# ETH_PHY_RGMII.net
KiCad netlist of a schematic drawn in Altium Designer
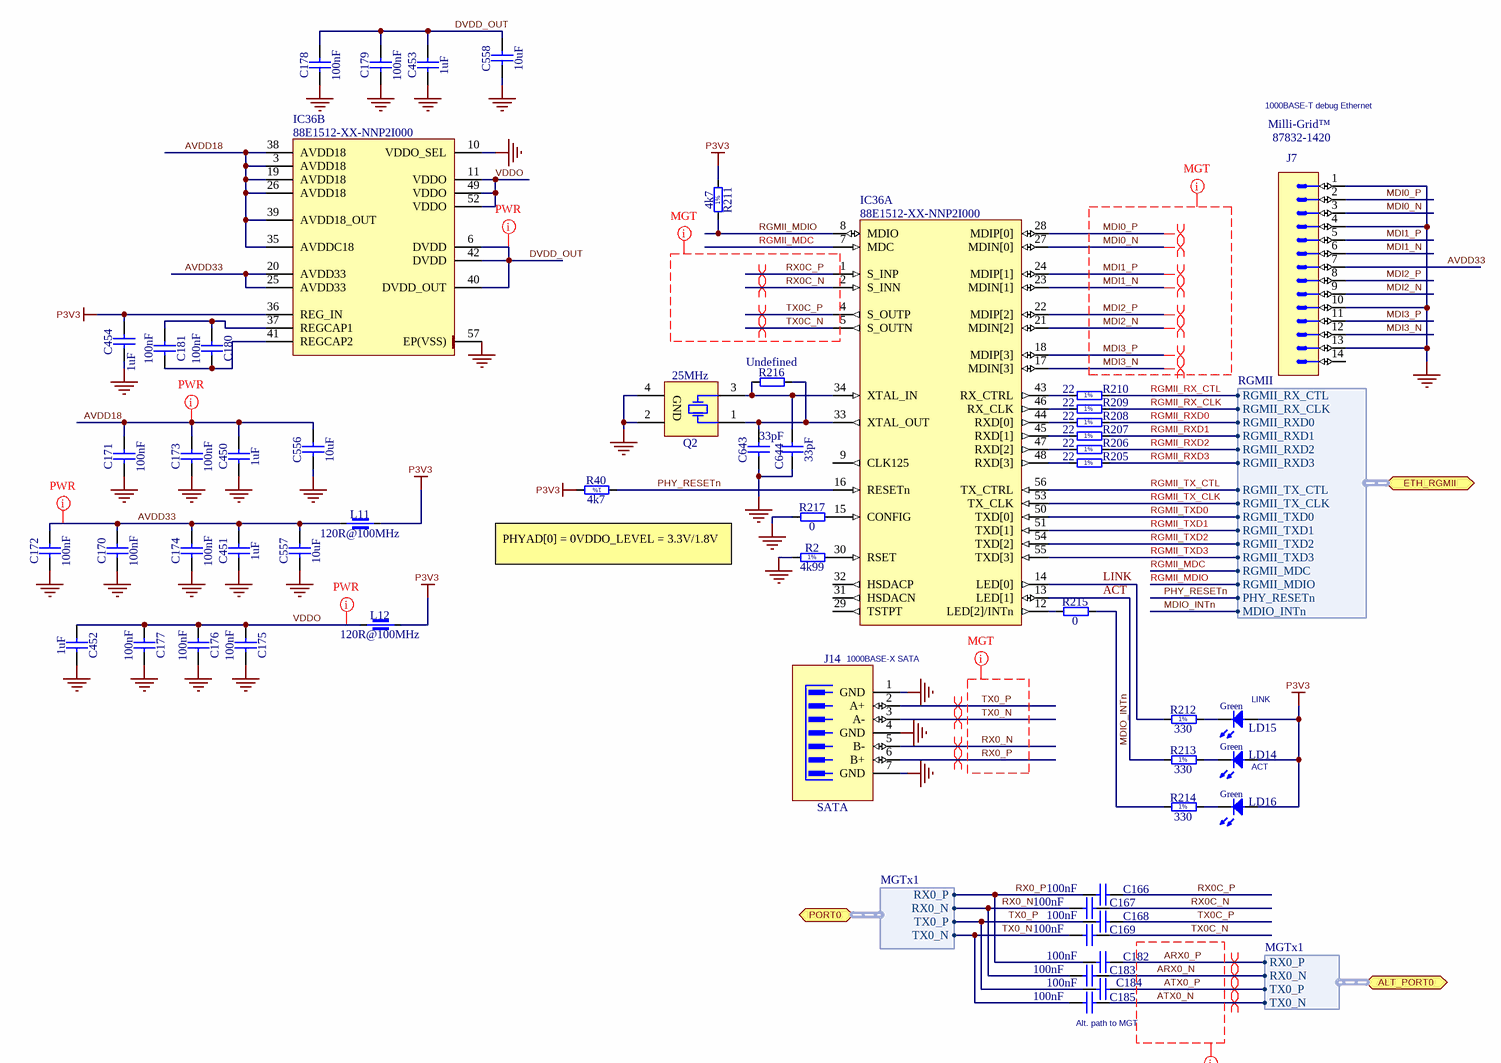
[diagram p0: ETH_PHY_RGMII.SchDoc]

(export (version "E")
  (design (tool "Eeschema 10.0.6"))
  (components
    (comp (ref "C166")
      (value "100nF")
      (footprint "CAPC0603X33N")
      (description "Non-polarised capacitor")
      (fields
        (field (name "MANUFACTURER PART NUMBER") "CC0201_100NF_6.3V_10%_X5R")
        (field (name "MANUFACTURER") "GENERIC")
        (field (name "AUTHOR") "CERN DEM JLC")
      )
      (libsource (lib "Capacitors") (part "Capacitor - non polarized"))
    )
    (comp (ref "C167")
      (value "100nF")
      (footprint "CAPC0603X33N")
      (description "Non-polarised capacitor")
      (fields
        (field (name "MANUFACTURER PART NUMBER") "CC0201_100NF_6.3V_10%_X5R")
        (field (name "MANUFACTURER") "GENERIC")
        (field (name "AUTHOR") "CERN DEM JLC")
      )
      (libsource (lib "Capacitors") (part "Capacitor - non polarized"))
    )
    (comp (ref "C168")
      (value "100nF")
      (footprint "CAPC0603X33N")
      (description "Non-polarised capacitor")
      (fields
        (field (name "MANUFACTURER PART NUMBER") "CC0201_100NF_6.3V_10%_X5R")
        (field (name "MANUFACTURER") "GENERIC")
        (field (name "AUTHOR") "CERN DEM JLC")
      )
      (libsource (lib "Capacitors") (part "Capacitor - non polarized"))
    )
    (comp (ref "C169")
      (value "100nF")
      (footprint "CAPC0603X33N")
      (description "Non-polarised capacitor")
      (fields
        (field (name "MANUFACTURER PART NUMBER") "CC0201_100NF_6.3V_10%_X5R")
        (field (name "MANUFACTURER") "GENERIC")
        (field (name "AUTHOR") "CERN DEM JLC")
      )
      (libsource (lib "Capacitors") (part "Capacitor - non polarized"))
    )
    (comp (ref "C170")
      (value "100nF")
      (footprint "CAPC0603X33N")
      (description "Non-polarised capacitor")
      (fields
        (field (name "MANUFACTURER PART NUMBER") "CC0201_100NF_6.3V_10%_X5R")
        (field (name "MANUFACTURER") "GENERIC")
        (field (name "AUTHOR") "CERN DEM JLC")
      )
      (libsource (lib "Capacitors") (part "Capacitor - non polarized"))
    )
    (comp (ref "C171")
      (value "100nF")
      (footprint "CAPC0603X33N")
      (description "Non-polarised capacitor")
      (fields
        (field (name "MANUFACTURER PART NUMBER") "CC0201_100NF_6.3V_10%_X5R")
        (field (name "MANUFACTURER") "GENERIC")
        (field (name "AUTHOR") "CERN DEM JLC")
      )
      (libsource (lib "Capacitors") (part "Capacitor - non polarized"))
    )
    (comp (ref "C172")
      (value "100nF")
      (footprint "CAPC0603X33N")
      (description "Non-polarised capacitor")
      (fields
        (field (name "MANUFACTURER PART NUMBER") "CC0201_100NF_6.3V_10%_X5R")
        (field (name "MANUFACTURER") "GENERIC")
        (field (name "AUTHOR") "CERN DEM JLC")
      )
      (libsource (lib "Capacitors") (part "Capacitor - non polarized"))
    )
    (comp (ref "C173")
      (value "100nF")
      (footprint "CAPC0603X33N")
      (description "Non-polarised capacitor")
      (fields
        (field (name "MANUFACTURER PART NUMBER") "CC0201_100NF_6.3V_10%_X5R")
        (field (name "MANUFACTURER") "GENERIC")
        (field (name "AUTHOR") "CERN DEM JLC")
      )
      (libsource (lib "Capacitors") (part "Capacitor - non polarized"))
    )
    (comp (ref "C174")
      (value "100nF")
      (footprint "CAPC0603X33N")
      (description "Non-polarised capacitor")
      (fields
        (field (name "MANUFACTURER PART NUMBER") "CC0201_100NF_6.3V_10%_X5R")
        (field (name "MANUFACTURER") "GENERIC")
        (field (name "AUTHOR") "CERN DEM JLC")
      )
      (libsource (lib "Capacitors") (part "Capacitor - non polarized"))
    )
    (comp (ref "C175")
      (value "100nF")
      (footprint "CAPC0603X33N")
      (description "Non-polarised capacitor")
      (fields
        (field (name "MANUFACTURER PART NUMBER") "CC0201_100NF_6.3V_10%_X5R")
        (field (name "MANUFACTURER") "GENERIC")
        (field (name "AUTHOR") "CERN DEM JLC")
      )
      (libsource (lib "Capacitors") (part "Capacitor - non polarized"))
    )
    (comp (ref "C176")
      (value "100nF")
      (footprint "CAPC0603X33N")
      (description "Non-polarised capacitor")
      (fields
        (field (name "MANUFACTURER PART NUMBER") "CC0201_100NF_6.3V_10%_X5R")
        (field (name "MANUFACTURER") "GENERIC")
        (field (name "AUTHOR") "CERN DEM JLC")
      )
      (libsource (lib "Capacitors") (part "Capacitor - non polarized"))
    )
    (comp (ref "C177")
      (value "100nF")
      (footprint "CAPC0603X33N")
      (description "Non-polarised capacitor")
      (fields
        (field (name "MANUFACTURER PART NUMBER") "CC0201_100NF_6.3V_10%_X5R")
        (field (name "MANUFACTURER") "GENERIC")
        (field (name "AUTHOR") "CERN DEM JLC")
      )
      (libsource (lib "Capacitors") (part "Capacitor - non polarized"))
    )
    (comp (ref "C178")
      (value "100nF")
      (footprint "CAPC0603X33N")
      (description "Non-polarised capacitor")
      (fields
        (field (name "MANUFACTURER PART NUMBER") "CC0201_100NF_6.3V_10%_X5R")
        (field (name "MANUFACTURER") "GENERIC")
        (field (name "AUTHOR") "CERN DEM JLC")
      )
      (libsource (lib "Capacitors") (part "Capacitor - non polarized"))
    )
    (comp (ref "C179")
      (value "100nF")
      (footprint "CAPC0603X33N")
      (description "Non-polarised capacitor")
      (fields
        (field (name "MANUFACTURER PART NUMBER") "CC0201_100NF_6.3V_10%_X5R")
        (field (name "MANUFACTURER") "GENERIC")
        (field (name "AUTHOR") "CERN DEM JLC")
      )
      (libsource (lib "Capacitors") (part "Capacitor - non polarized"))
    )
    (comp (ref "C180")
      (value "100nF")
      (footprint "CAPC0603X33N")
      (description "Non-polarised capacitor")
      (fields
        (field (name "MANUFACTURER PART NUMBER") "CC0201_100NF_6.3V_10%_X5R")
        (field (name "MANUFACTURER") "GENERIC")
        (field (name "AUTHOR") "CERN DEM JLC")
      )
      (libsource (lib "Capacitors") (part "Capacitor - non polarized"))
    )
    (comp (ref "C181")
      (value "100nF")
      (footprint "CAPC0603X33N")
      (description "Non-polarised capacitor")
      (fields
        (field (name "MANUFACTURER PART NUMBER") "CC0201_100NF_6.3V_10%_X5R")
        (field (name "MANUFACTURER") "GENERIC")
        (field (name "AUTHOR") "CERN DEM JLC")
      )
      (libsource (lib "Capacitors") (part "Capacitor - non polarized"))
    )
    (comp (ref "C182")
      (value "100nF")
      (footprint "CAPC0603X33N")
      (description "Non-polarised capacitor")
      (fields
        (field (name "MANUFACTURER PART NUMBER") "CC0201_100NF_6.3V_10%_X5R")
        (field (name "MANUFACTURER") "GENERIC")
        (field (name "AUTHOR") "CERN DEM JLC")
      )
      (libsource (lib "Capacitors") (part "Capacitor - non polarized"))
    )
    (comp (ref "C183")
      (value "100nF")
      (footprint "CAPC0603X33N")
      (description "Non-polarised capacitor")
      (fields
        (field (name "MANUFACTURER PART NUMBER") "CC0201_100NF_6.3V_10%_X5R")
        (field (name "MANUFACTURER") "GENERIC")
        (field (name "AUTHOR") "CERN DEM JLC")
      )
      (libsource (lib "Capacitors") (part "Capacitor - non polarized"))
    )
    (comp (ref "C184")
      (value "100nF")
      (footprint "CAPC0603X33N")
      (description "Non-polarised capacitor")
      (fields
        (field (name "MANUFACTURER PART NUMBER") "CC0201_100NF_6.3V_10%_X5R")
        (field (name "MANUFACTURER") "GENERIC")
        (field (name "AUTHOR") "CERN DEM JLC")
      )
      (libsource (lib "Capacitors") (part "Capacitor - non polarized"))
    )
    (comp (ref "C185")
      (value "100nF")
      (footprint "CAPC0603X33N")
      (description "Non-polarised capacitor")
      (fields
        (field (name "MANUFACTURER PART NUMBER") "CC0201_100NF_6.3V_10%_X5R")
        (field (name "MANUFACTURER") "GENERIC")
        (field (name "AUTHOR") "CERN DEM JLC")
      )
      (libsource (lib "Capacitors") (part "Capacitor - non polarized"))
    )
    (comp (ref "C450")
      (value "1uF")
      (footprint "CAPC1005X55N")
      (description "Non-polarised capacitor")
      (fields
        (field (name "MANUFACTURER PART NUMBER") "CC0402_1UF_16V_10%_X5R")
        (field (name "MANUFACTURER") "GENERIC")
        (field (name "AUTHOR") "CERN DEM JLC")
      )
      (libsource (lib "Capacitors") (part "Capacitor - non polarized"))
    )
    (comp (ref "C451")
      (value "1uF")
      (footprint "CAPC1005X55N")
      (description "Non-polarised capacitor")
      (fields
        (field (name "MANUFACTURER PART NUMBER") "CC0402_1UF_16V_10%_X5R")
        (field (name "MANUFACTURER") "GENERIC")
        (field (name "AUTHOR") "CERN DEM JLC")
      )
      (libsource (lib "Capacitors") (part "Capacitor - non polarized"))
    )
    (comp (ref "C452")
      (value "1uF")
      (footprint "CAPC1005X55N")
      (description "Non-polarised capacitor")
      (fields
        (field (name "MANUFACTURER PART NUMBER") "CC0402_1UF_16V_10%_X5R")
        (field (name "MANUFACTURER") "GENERIC")
        (field (name "AUTHOR") "CERN DEM JLC")
      )
      (libsource (lib "Capacitors") (part "Capacitor - non polarized"))
    )
    (comp (ref "C453")
      (value "1uF")
      (footprint "CAPC1005X55N")
      (description "Non-polarised capacitor")
      (fields
        (field (name "MANUFACTURER PART NUMBER") "CC0402_1UF_16V_10%_X5R")
        (field (name "MANUFACTURER") "GENERIC")
        (field (name "AUTHOR") "CERN DEM JLC")
      )
      (libsource (lib "Capacitors") (part "Capacitor - non polarized"))
    )
    (comp (ref "C454")
      (value "1uF")
      (footprint "CAPC1005X55N")
      (description "Non-polarised capacitor")
      (fields
        (field (name "MANUFACTURER PART NUMBER") "CC0402_1UF_16V_10%_X5R")
        (field (name "MANUFACTURER") "GENERIC")
        (field (name "AUTHOR") "CERN DEM JLC")
      )
      (libsource (lib "Capacitors") (part "Capacitor - non polarized"))
    )
    (comp (ref "C556")
      (value "10uF")
      (footprint "CAPC1608X87N")
      (description "Non-polarised capacitor")
      (fields
        (field (name "MANUFACTURER PART NUMBER") "CC0603_10uF_6.3V_20%_X5R")
        (field (name "MANUFACTURER") "GENERIC")
        (field (name "AUTHOR") "CERN DEM JLC")
      )
      (libsource (lib "Capacitors") (part "Capacitor - non polarized"))
    )
    (comp (ref "C557")
      (value "10uF")
      (footprint "CAPC1608X87N")
      (description "Non-polarised capacitor")
      (fields
        (field (name "MANUFACTURER PART NUMBER") "CC0603_10uF_6.3V_20%_X5R")
        (field (name "MANUFACTURER") "GENERIC")
        (field (name "AUTHOR") "CERN DEM JLC")
      )
      (libsource (lib "Capacitors") (part "Capacitor - non polarized"))
    )
    (comp (ref "C558")
      (value "10uF")
      (footprint "CAPC1608X87N")
      (description "Non-polarised capacitor")
      (fields
        (field (name "MANUFACTURER PART NUMBER") "CC0603_10uF_6.3V_20%_X5R")
        (field (name "MANUFACTURER") "GENERIC")
        (field (name "AUTHOR") "CERN DEM JLC")
      )
      (libsource (lib "Capacitors") (part "Capacitor - non polarized"))
    )
    (comp (ref "C643")
      (value "33pF")
      (footprint "CAPC1005X55N")
      (description "Non-polarised capacitor")
      (fields
        (field (name "MANUFACTURER PART NUMBER") "CC0402_33PF_50V_5%_C0G")
        (field (name "MANUFACTURER") "GENERIC")
        (field (name "AUTHOR") "CERN DEM JLC")
      )
      (libsource (lib "Capacitors") (part "Capacitor - non polarized"))
    )
    (comp (ref "C644")
      (value "33pF")
      (footprint "CAPC1005X55N")
      (description "Non-polarised capacitor")
      (fields
        (field (name "MANUFACTURER PART NUMBER") "CC0402_33PF_50V_5%_C0G")
        (field (name "MANUFACTURER") "GENERIC")
        (field (name "AUTHOR") "CERN DEM JLC")
      )
      (libsource (lib "Capacitors") (part "Capacitor - non polarized"))
    )
    (comp (ref "IC36")
      (value "88E1512-XX-NNP2I000")
      (footprint "QFN50P800X800X100-57N-S437")
      (description "Alaska Integrated 10/100/1000 Mbps Energy Efficient Ethernet Transceiver")
      (fields (field (name "MANUFACTURER") "MARVELL  TECHNOLOGY") (field (name "AUTHOR") "CERN DEM JLC"))
      (libsource (lib "ICs And Semiconductors") (part "88E1512-XX-NNP2I000"))
    )
    (comp (ref "J7")
      (value "Milli-Grid™")
      (footprint "MOLEX_87832-1420")
      (description "Connector 14 Male")
      (fields
        (field (name "MANUFACTURER PART NUMBER") "87832-1420")
        (field (name "MANUFACTURER") "MOLEX")
        (field (name "PART NUMBER") "MOLEX_87832-1420")
        (field (name "AUTHOR") "CERN DEM JLC")
      )
      (libsource (lib "Connectors") (part "Connector 14 Male"))
    )
    (comp (ref "J14")
      (value "SATA")
      (footprint "MOLEX_67800-5005")
      (description "7 Pin SATA Receptacle")
      (fields
        (field (name "PART NUMBER") "MOLEX_67800-5005")
        (field (name "MANUFACTURER") "MOLEX")
        (field (name "AUTHOR") "CERN DEM MR")
      )
      (libsource (lib "Connectors") (part "Connector SATA 7 Male"))
    )
    (comp (ref "L11")
      (value "120R@100MHz")
      (footprint "INDC1005X55N")
      (fields
        (field (name "MANUFACTURER PART NUMBER") "BLM15PX121SN1D")
        (field (name "MANUFACTURER") "MURATA")
        (field (name "PART NUMBER") "IND0402_MURATA_BLM15PX121SN1D")
        (field (name "AUTHOR") "CERN DEM JMW")
      )
      (libsource (lib "Inductors & Transformers") (part "Ferrite Bead"))
    )
    (comp (ref "L12")
      (value "120R@100MHz")
      (footprint "INDC1005X55N")
      (fields
        (field (name "MANUFACTURER PART NUMBER") "BLM15PX121SN1D")
        (field (name "MANUFACTURER") "MURATA")
        (field (name "PART NUMBER") "IND0402_MURATA_BLM15PX121SN1D")
        (field (name "AUTHOR") "CERN DEM JMW")
      )
      (libsource (lib "") (part "Ferrite Bead_1"))
    )
    (comp (ref "LD14")
      (value "Green")
      (footprint "LED_AVAGO_HSME-C120")
      (description "LED Green 1C 2A")
      (fields
        (field (name "MANUFACTURER PART NUMBER") "HSME-C120")
        (field (name "MANUFACTURER") "AVAGO TECHNOLOGIES")
        (field (name "AUTHOR") "CERN DEM JMW")
      )
      (libsource (lib "ICs And Semiconductors") (part "LED Green 1C 2A"))
    )
    (comp (ref "LD15")
      (value "Green")
      (footprint "LED_AVAGO_HSME-C120")
      (description "LED Green 1C 2A")
      (fields
        (field (name "MANUFACTURER PART NUMBER") "HSME-C120")
        (field (name "MANUFACTURER") "AVAGO TECHNOLOGIES")
        (field (name "AUTHOR") "CERN DEM JMW")
      )
      (libsource (lib "ICs And Semiconductors") (part "LED Green 1C 2A"))
    )
    (comp (ref "LD16")
      (value "Green")
      (footprint "LED_AVAGO_HSME-C120")
      (description "LED Green 1C 2A")
      (fields
        (field (name "MANUFACTURER PART NUMBER") "HSME-C120")
        (field (name "MANUFACTURER") "AVAGO TECHNOLOGIES")
        (field (name "AUTHOR") "CERN DEM JMW")
      )
      (libsource (lib "ICs And Semiconductors") (part "LED Green 1C 2A"))
    )
    (comp (ref "Q2")
      (value "25MHz")
      (footprint "XTAL_TXC_8Y")
      (description "Crystal 4 pins 1=XTAL Control 2=GND3=XTAL 4=GND")
      (fields
        (field (name "MANUFACTURER PART NUMBER") "8Y-25.000MAAJ-T")
        (field (name "MANUFACTURER") "TXC CORPORATION")
        (field (name "AUTHOR") "CERN DEM JLC")
      )
      (libsource (lib "ICs And Semiconductors") (part "Quartz Crystal 1X 2GND 3X 4GND"))
    )
    (comp (ref "R2")
      (value "4k99")
      (footprint "RESC1608X55N")
      (description "Resistor - 1%")
      (fields
        (field (name "MANUFACTURER PART NUMBER") "R0603_4K99_1%_0.063W_50PPM")
        (field (name "MANUFACTURER") "GENERIC")
        (field (name "AUTHOR") "CERN DEM JLC")
      )
      (libsource (lib "Resistors") (part "Resistor - 1%"))
    )
    (comp (ref "R40")
      (value "4k7")
      (footprint "RESC1005X40N")
      (description "Resistor - 1%")
      (fields
        (field (name "MANUFACTURER PART NUMBER") "R0402_4K7_1%_0.0625W_100PPM")
        (field (name "MANUFACTURER") "GENERIC")
        (field (name "AUTHOR") "CERN DEM JLC")
      )
      (libsource (lib "Resistors") (part "Resistor - 1%"))
    )
    (comp (ref "R205")
      (value "22")
      (footprint "RESC1005X40N")
      (description "Resistor - 1%")
      (fields
        (field (name "MANUFACTURER PART NUMBER") "R0402_22R_1%_0.0625W_100PPM")
        (field (name "MANUFACTURER") "GENERIC")
        (field (name "AUTHOR") "CERN DEM JLC")
      )
      (libsource (lib "Resistors") (part "Resistor - 1%"))
    )
    (comp (ref "R206")
      (value "22")
      (footprint "RESC1005X40N")
      (description "Resistor - 1%")
      (fields
        (field (name "MANUFACTURER PART NUMBER") "R0402_22R_1%_0.0625W_100PPM")
        (field (name "MANUFACTURER") "GENERIC")
        (field (name "AUTHOR") "CERN DEM JLC")
      )
      (libsource (lib "Resistors") (part "Resistor - 1%"))
    )
    (comp (ref "R207")
      (value "22")
      (footprint "RESC1005X40N")
      (description "Resistor - 1%")
      (fields
        (field (name "MANUFACTURER PART NUMBER") "R0402_22R_1%_0.0625W_100PPM")
        (field (name "MANUFACTURER") "GENERIC")
        (field (name "AUTHOR") "CERN DEM JLC")
      )
      (libsource (lib "Resistors") (part "Resistor - 1%"))
    )
    (comp (ref "R208")
      (value "22")
      (footprint "RESC1005X40N")
      (description "Resistor - 1%")
      (fields
        (field (name "MANUFACTURER PART NUMBER") "R0402_22R_1%_0.0625W_100PPM")
        (field (name "MANUFACTURER") "GENERIC")
        (field (name "AUTHOR") "CERN DEM JLC")
      )
      (libsource (lib "Resistors") (part "Resistor - 1%"))
    )
    (comp (ref "R209")
      (value "22")
      (footprint "RESC1005X40N")
      (description "Resistor - 1%")
      (fields
        (field (name "MANUFACTURER PART NUMBER") "R0402_22R_1%_0.0625W_100PPM")
        (field (name "MANUFACTURER") "GENERIC")
        (field (name "AUTHOR") "CERN DEM JLC")
      )
      (libsource (lib "Resistors") (part "Resistor - 1%"))
    )
    (comp (ref "R210")
      (value "22")
      (footprint "RESC1005X40N")
      (description "Resistor - 1%")
      (fields
        (field (name "MANUFACTURER PART NUMBER") "R0402_22R_1%_0.0625W_100PPM")
        (field (name "MANUFACTURER") "GENERIC")
        (field (name "AUTHOR") "CERN DEM JLC")
      )
      (libsource (lib "Resistors") (part "Resistor - 1%"))
    )
    (comp (ref "R211")
      (value "4k7")
      (footprint "RESC1005X40N")
      (description "Resistor - 1%")
      (fields
        (field (name "MANUFACTURER PART NUMBER") "R0402_4K7_1%_0.0625W_100PPM")
        (field (name "MANUFACTURER") "GENERIC")
        (field (name "AUTHOR") "CERN DEM JLC")
      )
      (libsource (lib "Resistors") (part "Resistor - 1%"))
    )
    (comp (ref "R212")
      (value "330")
      (footprint "RESC1005X40N")
      (description "Resistor - 1%")
      (fields
        (field (name "MANUFACTURER PART NUMBER") "R0402_330R_1%_0.0625W_100PPM")
        (field (name "MANUFACTURER") "GENERIC")
        (field (name "AUTHOR") "CERN DEM JLC")
      )
      (libsource (lib "Resistors") (part "Resistor - 1%"))
    )
    (comp (ref "R213")
      (value "330")
      (footprint "RESC1005X40N")
      (description "Resistor - 1%")
      (fields
        (field (name "MANUFACTURER PART NUMBER") "R0402_330R_1%_0.0625W_100PPM")
        (field (name "MANUFACTURER") "GENERIC")
        (field (name "AUTHOR") "CERN DEM JLC")
      )
      (libsource (lib "Resistors") (part "Resistor - 1%"))
    )
    (comp (ref "R214")
      (value "330")
      (footprint "RESC1005X40N")
      (description "Resistor - 1%")
      (fields
        (field (name "MANUFACTURER PART NUMBER") "R0402_330R_1%_0.0625W_100PPM")
        (field (name "MANUFACTURER") "GENERIC")
        (field (name "AUTHOR") "CERN DEM JLC")
      )
      (libsource (lib "Resistors") (part "Resistor - 1%"))
    )
    (comp (ref "R215")
      (value "0")
      (footprint "RESC1005X40N")
      (description "Resistor")
      (fields
        (field (name "MANUFACTURER PART NUMBER") "R0402_0R_JUMPER")
        (field (name "MANUFACTURER") "GENERIC")
        (field (name "AUTHOR") "CERN DEM JLC")
      )
      (libsource (lib "Resistors") (part "Resistor"))
    )
    (comp (ref "R216")
      (value "Undefined")
      (footprint "RESC1005X40N")
      (description "Resistor")
      (fields
        (field (name "MANUFACTURER PART NUMBER") "R0402_NO-VALUE")
        (field (name "AUTHOR") "CERN DEM JLC")
      )
      (libsource (lib "Resistors") (part "Resistor"))
    )
    (comp (ref "R217")
      (value "0")
      (footprint "RESC1005X40N")
      (description "Resistor")
      (fields
        (field (name "MANUFACTURER PART NUMBER") "R0402_0R_JUMPER")
        (field (name "MANUFACTURER") "GENERIC")
        (field (name "AUTHOR") "CERN DEM JLC")
      )
      (libsource (lib "Resistors") (part "Resistor"))
    )
  )
  (nets
    (net (code "3") (name "/ACT") (class "Default")
      (node (ref "IC36") (pin "13") (pinfunction "LED[1]_13") (pintype "bidirectional"))
      (node (ref "R213") (pin "1") (pinfunction "1_1") (pintype "passive"))
    )
    (net (code "4") (name "/ARX0_N") (class "Default")
      (node (ref "C183") (pin "2") (pinfunction "2_2") (pintype "passive"))
    )
    (net (code "5") (name "/ARX0_P") (class "Default")
      (node (ref "C182") (pin "2") (pinfunction "2_2") (pintype "passive"))
    )
    (net (code "6") (name "/ATX0_N") (class "Default")
      (node (ref "C185") (pin "2") (pinfunction "2_2") (pintype "passive"))
    )
    (net (code "7") (name "/ATX0_P") (class "Default")
      (node (ref "C184") (pin "2") (pinfunction "2_2") (pintype "passive"))
    )
    (net (code "8") (name "/AVDD18") (class "Default")
      (node (ref "C171") (pin "2") (pinfunction "2_2") (pintype "passive"))
      (node (ref "C173") (pin "2") (pinfunction "2_2") (pintype "passive"))
      (node (ref "C450") (pin "2") (pinfunction "2_2") (pintype "passive"))
      (node (ref "C556") (pin "2") (pinfunction "2_2") (pintype "passive"))
      (node (ref "IC36") (pin "19") (pinfunction "AVDD18_19") (pintype "power_in"))
      (node (ref "IC36") (pin "26") (pinfunction "AVDD18_26") (pintype "power_in"))
      (node (ref "IC36") (pin "3") (pinfunction "AVDD18_3") (pintype "power_in"))
      (node (ref "IC36") (pin "35") (pinfunction "AVDDC18_35") (pintype "power_in"))
      (node (ref "IC36") (pin "38") (pinfunction "AVDD18_38") (pintype "power_in"))
      (node (ref "IC36") (pin "39") (pinfunction "AVDD18_OUT_39") (pintype "power_in"))
    )
    (net (code "9") (name "/AVDD33") (class "Default")
      (node (ref "C170") (pin "2") (pinfunction "2_2") (pintype "passive"))
      (node (ref "C172") (pin "2") (pinfunction "2_2") (pintype "passive"))
      (node (ref "C174") (pin "2") (pinfunction "2_2") (pintype "passive"))
      (node (ref "C451") (pin "2") (pinfunction "2_2") (pintype "passive"))
      (node (ref "C557") (pin "2") (pinfunction "2_2") (pintype "passive"))
      (node (ref "IC36") (pin "20") (pinfunction "AVDD33_20") (pintype "power_in"))
      (node (ref "IC36") (pin "25") (pinfunction "AVDD33_25") (pintype "power_in"))
      (node (ref "J7") (pin "7") (pinfunction "7_7") (pintype "bidirectional"))
      (node (ref "L11") (pin "1") (pinfunction "1_1") (pintype "passive"))
    )
    (net (code "10") (name "/DVDD_OUT") (class "Default")
      (node (ref "C178") (pin "2") (pinfunction "2_2") (pintype "passive"))
      (node (ref "C179") (pin "2") (pinfunction "2_2") (pintype "passive"))
      (node (ref "C453") (pin "2") (pinfunction "2_2") (pintype "passive"))
      (node (ref "C558") (pin "2") (pinfunction "2_2") (pintype "passive"))
      (node (ref "IC36") (pin "40") (pinfunction "DVDD_OUT_40") (pintype "power_in"))
      (node (ref "IC36") (pin "42") (pinfunction "DVDD_42") (pintype "power_in"))
      (node (ref "IC36") (pin "6") (pinfunction "DVDD_6") (pintype "power_in"))
    )
    (net (code "11") (name "/LINK") (class "Default")
      (node (ref "IC36") (pin "14") (pinfunction "LED[0]_14") (pintype "output"))
      (node (ref "R212") (pin "1") (pinfunction "1_1") (pintype "passive"))
    )
    (net (code "12") (name "/MDI0_N") (class "Default")
      (node (ref "IC36") (pin "27") (pinfunction "MDIN[0]_27") (pintype "bidirectional"))
      (node (ref "J7") (pin "3") (pinfunction "3_3") (pintype "bidirectional"))
    )
    (net (code "13") (name "/MDI0_P") (class "Default")
      (node (ref "IC36") (pin "28") (pinfunction "MDIP[0]_28") (pintype "bidirectional"))
      (node (ref "J7") (pin "2") (pinfunction "2_2") (pintype "bidirectional"))
    )
    (net (code "14") (name "/MDI1_N") (class "Default")
      (node (ref "IC36") (pin "23") (pinfunction "MDIN[1]_23") (pintype "bidirectional"))
      (node (ref "J7") (pin "6") (pinfunction "6_6") (pintype "bidirectional"))
    )
    (net (code "15") (name "/MDI1_P") (class "Default")
      (node (ref "IC36") (pin "24") (pinfunction "MDIP[1]_24") (pintype "bidirectional"))
      (node (ref "J7") (pin "5") (pinfunction "5_5") (pintype "bidirectional"))
    )
    (net (code "16") (name "/MDI2_N") (class "Default")
      (node (ref "IC36") (pin "21") (pinfunction "MDIN[2]_21") (pintype "bidirectional"))
      (node (ref "J7") (pin "9") (pinfunction "9_9") (pintype "bidirectional"))
    )
    (net (code "17") (name "/MDI2_P") (class "Default")
      (node (ref "IC36") (pin "22") (pinfunction "MDIP[2]_22") (pintype "bidirectional"))
      (node (ref "J7") (pin "8") (pinfunction "8_8") (pintype "bidirectional"))
    )
    (net (code "18") (name "/MDI3_N") (class "Default")
      (node (ref "IC36") (pin "17") (pinfunction "MDIN[3]_17") (pintype "bidirectional"))
      (node (ref "J7") (pin "12") (pinfunction "12_12") (pintype "bidirectional"))
    )
    (net (code "19") (name "/MDI3_P") (class "Default")
      (node (ref "IC36") (pin "18") (pinfunction "MDIP[3]_18") (pintype "bidirectional"))
      (node (ref "J7") (pin "11") (pinfunction "11_11") (pintype "bidirectional"))
    )
    (net (code "20") (name "/MDIO_INTn") (class "Default")
      (node (ref "R214") (pin "1") (pinfunction "1_1") (pintype "passive"))
      (node (ref "R215") (pin "2") (pinfunction "2_2") (pintype "passive"))
    )
    (net (code "21") (name "/PHY_RESETn") (class "Default")
      (node (ref "IC36") (pin "16") (pinfunction "RESETn_16") (pintype "input"))
      (node (ref "R40") (pin "1") (pinfunction "1_1") (pintype "passive"))
    )
    (net (code "22") (name "/RGMII_MDC") (class "Default")
      (node (ref "IC36") (pin "7") (pinfunction "MDC_7") (pintype "input"))
    )
    (net (code "23") (name "/RGMII_MDIO") (class "Default")
      (node (ref "IC36") (pin "8") (pinfunction "MDIO_8") (pintype "bidirectional"))
      (node (ref "R211") (pin "1") (pinfunction "1_1") (pintype "passive"))
    )
    (net (code "24") (name "/RGMII_RXD0") (class "Default")
      (node (ref "R208") (pin "2") (pinfunction "2_2") (pintype "passive"))
    )
    (net (code "25") (name "/RGMII_RXD1") (class "Default")
      (node (ref "R207") (pin "2") (pinfunction "2_2") (pintype "passive"))
    )
    (net (code "26") (name "/RGMII_RXD2") (class "Default")
      (node (ref "R206") (pin "2") (pinfunction "2_2") (pintype "passive"))
    )
    (net (code "27") (name "/RGMII_RXD3") (class "Default")
      (node (ref "R205") (pin "2") (pinfunction "2_2") (pintype "passive"))
    )
    (net (code "28") (name "/RGMII_RX_CLK") (class "Default")
      (node (ref "R209") (pin "2") (pinfunction "2_2") (pintype "passive"))
    )
    (net (code "29") (name "/RGMII_RX_CTL") (class "Default")
      (node (ref "R210") (pin "2") (pinfunction "2_2") (pintype "passive"))
    )
    (net (code "30") (name "/RGMII_TXD0") (class "Default")
      (node (ref "IC36") (pin "50") (pinfunction "TXD[0]_50") (pintype "input"))
    )
    (net (code "31") (name "/RGMII_TXD1") (class "Default")
      (node (ref "IC36") (pin "51") (pinfunction "TXD[1]_51") (pintype "input"))
    )
    (net (code "32") (name "/RGMII_TXD2") (class "Default")
      (node (ref "IC36") (pin "54") (pinfunction "TXD[2]_54") (pintype "input"))
    )
    (net (code "33") (name "/RGMII_TXD3") (class "Default")
      (node (ref "IC36") (pin "55") (pinfunction "TXD[3]_55") (pintype "input"))
    )
    (net (code "34") (name "/RGMII_TX_CLK") (class "Default")
      (node (ref "IC36") (pin "53") (pinfunction "TX_CLK_53") (pintype "input"))
    )
    (net (code "35") (name "/RGMII_TX_CTL") (class "Default")
      (node (ref "IC36") (pin "56") (pinfunction "TX_CTRL_56") (pintype "input"))
    )
    (net (code "36") (name "/RX0C_N") (class "Default")
      (node (ref "C167") (pin "2") (pinfunction "2_2") (pintype "passive"))
      (node (ref "IC36") (pin "2") (pinfunction "S_INN_2") (pintype "input"))
    )
    (net (code "37") (name "/RX0C_P") (class "Default")
      (node (ref "C166") (pin "2") (pinfunction "2_2") (pintype "passive"))
      (node (ref "IC36") (pin "1") (pinfunction "S_INP_1") (pintype "input"))
    )
    (net (code "38") (name "/RX0_N") (class "Default")
      (node (ref "C167") (pin "1") (pinfunction "1_1") (pintype "passive"))
      (node (ref "C183") (pin "1") (pinfunction "1_1") (pintype "passive"))
      (node (ref "J14") (pin "5") (pinfunction "B-_5") (pintype "bidirectional"))
    )
    (net (code "39") (name "/RX0_P") (class "Default")
      (node (ref "C166") (pin "1") (pinfunction "1_1") (pintype "passive"))
      (node (ref "C182") (pin "1") (pinfunction "1_1") (pintype "passive"))
      (node (ref "J14") (pin "6") (pinfunction "B+_6") (pintype "bidirectional"))
    )
    (net (code "40") (name "/TX0C_N") (class "Default")
      (node (ref "C169") (pin "2") (pinfunction "2_2") (pintype "passive"))
      (node (ref "IC36") (pin "5") (pinfunction "S_OUTN_5") (pintype "output"))
    )
    (net (code "41") (name "/TX0C_P") (class "Default")
      (node (ref "C168") (pin "2") (pinfunction "2_2") (pintype "passive"))
      (node (ref "IC36") (pin "4") (pinfunction "S_OUTP_4") (pintype "output"))
    )
    (net (code "42") (name "/TX0_N") (class "Default")
      (node (ref "C169") (pin "1") (pinfunction "1_1") (pintype "passive"))
      (node (ref "C185") (pin "1") (pinfunction "1_1") (pintype "passive"))
      (node (ref "J14") (pin "3") (pinfunction "A-_3") (pintype "bidirectional"))
    )
    (net (code "43") (name "/TX0_P") (class "Default")
      (node (ref "C168") (pin "1") (pinfunction "1_1") (pintype "passive"))
      (node (ref "C184") (pin "1") (pinfunction "1_1") (pintype "passive"))
      (node (ref "J14") (pin "2") (pinfunction "A+_2") (pintype "bidirectional"))
    )
    (net (code "44") (name "/VDDO") (class "Default")
      (node (ref "C175") (pin "2") (pinfunction "2_2") (pintype "passive"))
      (node (ref "C176") (pin "2") (pinfunction "2_2") (pintype "passive"))
      (node (ref "C177") (pin "2") (pinfunction "2_2") (pintype "passive"))
      (node (ref "C452") (pin "2") (pinfunction "2_2") (pintype "passive"))
      (node (ref "IC36") (pin "11") (pinfunction "VDDO_11") (pintype "power_in"))
      (node (ref "IC36") (pin "49") (pinfunction "VDDO_49") (pintype "power_in"))
      (node (ref "IC36") (pin "52") (pinfunction "VDDO_52") (pintype "power_in"))
      (node (ref "L12") (pin "2") (pinfunction "2_2") (pintype "passive"))
    )
    (net (code "47") (name "GND") (class "Default")
      (node (ref "C170") (pin "1") (pinfunction "1_1") (pintype "passive"))
      (node (ref "C171") (pin "1") (pinfunction "1_1") (pintype "passive"))
      (node (ref "C172") (pin "1") (pinfunction "1_1") (pintype "passive"))
      (node (ref "C173") (pin "1") (pinfunction "1_1") (pintype "passive"))
      (node (ref "C174") (pin "1") (pinfunction "1_1") (pintype "passive"))
      (node (ref "C175") (pin "1") (pinfunction "1_1") (pintype "passive"))
      (node (ref "C176") (pin "1") (pinfunction "1_1") (pintype "passive"))
      (node (ref "C177") (pin "1") (pinfunction "1_1") (pintype "passive"))
      (node (ref "C178") (pin "1") (pinfunction "1_1") (pintype "passive"))
      (node (ref "C179") (pin "1") (pinfunction "1_1") (pintype "passive"))
      (node (ref "C450") (pin "1") (pinfunction "1_1") (pintype "passive"))
      (node (ref "C451") (pin "1") (pinfunction "1_1") (pintype "passive"))
      (node (ref "C452") (pin "1") (pinfunction "1_1") (pintype "passive"))
      (node (ref "C453") (pin "1") (pinfunction "1_1") (pintype "passive"))
      (node (ref "C454") (pin "1") (pinfunction "1_1") (pintype "passive"))
      (node (ref "C556") (pin "1") (pinfunction "1_1") (pintype "passive"))
      (node (ref "C557") (pin "1") (pinfunction "1_1") (pintype "passive"))
      (node (ref "C558") (pin "1") (pinfunction "1_1") (pintype "passive"))
      (node (ref "C643") (pin "1") (pinfunction "1_1") (pintype "passive"))
      (node (ref "C644") (pin "1") (pinfunction "1_1") (pintype "passive"))
      (node (ref "IC36") (pin "10") (pinfunction "VDDO_SEL_10") (pintype "power_in"))
      (node (ref "IC36") (pin "57") (pinfunction "EP(VSS)_57") (pintype "power_in"))
      (node (ref "J14") (pin "1") (pinfunction "GND_1") (pintype "power_in"))
      (node (ref "J14") (pin "4") (pinfunction "GND_4") (pintype "power_in"))
      (node (ref "J14") (pin "7") (pinfunction "GND_7") (pintype "power_in"))
      (node (ref "J7") (pin "1") (pinfunction "1_1") (pintype "bidirectional"))
      (node (ref "J7") (pin "10") (pinfunction "10_10") (pintype "bidirectional"))
      (node (ref "J7") (pin "13") (pinfunction "13_13") (pintype "bidirectional"))
      (node (ref "J7") (pin "4") (pinfunction "4_4") (pintype "bidirectional"))
      (node (ref "Q2") (pin "2") (pinfunction "GND_2") (pintype "power_in"))
      (node (ref "Q2") (pin "4") (pinfunction "GND_4") (pintype "power_in"))
      (node (ref "R2") (pin "1") (pinfunction "1_1") (pintype "passive"))
      (node (ref "R217") (pin "1") (pinfunction "1_1") (pintype "passive"))
    )
    (net (code "48") (name "Net-(IC36A-CONFIG)") (class "Default")
      (node (ref "IC36") (pin "15") (pinfunction "CONFIG_15") (pintype "input"))
      (node (ref "R217") (pin "2") (pinfunction "2_2") (pintype "passive"))
    )
    (net (code "49") (name "Net-(IC36A-LED[2]{slash}INTn)") (class "Default")
      (node (ref "IC36") (pin "12") (pinfunction "LED[2]/INTn_12") (pintype "output"))
      (node (ref "R215") (pin "1") (pinfunction "1_1") (pintype "passive"))
    )
    (net (code "50") (name "Net-(IC36A-RSET)") (class "Default")
      (node (ref "IC36") (pin "30") (pinfunction "RSET_30") (pintype "input"))
      (node (ref "R2") (pin "2") (pinfunction "2_2") (pintype "passive"))
    )
    (net (code "51") (name "Net-(IC36A-RXD[0])") (class "Default")
      (node (ref "IC36") (pin "44") (pinfunction "RXD[0]_44") (pintype "output"))
      (node (ref "R208") (pin "1") (pinfunction "1_1") (pintype "passive"))
    )
    (net (code "52") (name "Net-(IC36A-RXD[1])") (class "Default")
      (node (ref "IC36") (pin "45") (pinfunction "RXD[1]_45") (pintype "output"))
      (node (ref "R207") (pin "1") (pinfunction "1_1") (pintype "passive"))
    )
    (net (code "53") (name "Net-(IC36A-RXD[2])") (class "Default")
      (node (ref "IC36") (pin "47") (pinfunction "RXD[2]_47") (pintype "output"))
      (node (ref "R206") (pin "1") (pinfunction "1_1") (pintype "passive"))
    )
    (net (code "54") (name "Net-(IC36A-RXD[3])") (class "Default")
      (node (ref "IC36") (pin "48") (pinfunction "RXD[3]_48") (pintype "output"))
      (node (ref "R205") (pin "1") (pinfunction "1_1") (pintype "passive"))
    )
    (net (code "55") (name "Net-(IC36A-RX_CLK)") (class "Default")
      (node (ref "IC36") (pin "46") (pinfunction "RX_CLK_46") (pintype "output"))
      (node (ref "R209") (pin "1") (pinfunction "1_1") (pintype "passive"))
    )
    (net (code "56") (name "Net-(IC36A-RX_CTRL)") (class "Default")
      (node (ref "IC36") (pin "43") (pinfunction "RX_CTRL_43") (pintype "output"))
      (node (ref "R210") (pin "1") (pinfunction "1_1") (pintype "passive"))
    )
    (net (code "57") (name "Net-(IC36A-XTAL_IN)") (class "Default")
      (node (ref "C644") (pin "2") (pinfunction "2_2") (pintype "passive"))
      (node (ref "IC36") (pin "34") (pinfunction "XTAL_IN_34") (pintype "input"))
      (node (ref "Q2") (pin "3") (pinfunction "X_3") (pintype "passive"))
      (node (ref "R216") (pin "1") (pinfunction "1_1") (pintype "passive"))
    )
    (net (code "58") (name "Net-(IC36A-XTAL_OUT)") (class "Default")
      (node (ref "C643") (pin "2") (pinfunction "2_2") (pintype "passive"))
      (node (ref "IC36") (pin "33") (pinfunction "XTAL_OUT_33") (pintype "output"))
      (node (ref "Q2") (pin "1") (pinfunction "X_1") (pintype "passive"))
      (node (ref "R216") (pin "2") (pinfunction "2_2") (pintype "passive"))
    )
    (net (code "59") (name "Net-(IC36B-REGCAP1)") (class "Default")
      (node (ref "C180") (pin "2") (pinfunction "2_2") (pintype "passive"))
      (node (ref "C181") (pin "2") (pinfunction "2_2") (pintype "passive"))
      (node (ref "IC36") (pin "37") (pinfunction "REGCAP1_37") (pintype "passive"))
    )
    (net (code "60") (name "Net-(IC36B-REGCAP2)") (class "Default")
      (node (ref "C180") (pin "1") (pinfunction "1_1") (pintype "passive"))
      (node (ref "C181") (pin "1") (pinfunction "1_1") (pintype "passive"))
      (node (ref "IC36") (pin "41") (pinfunction "REGCAP2_41") (pintype "passive"))
    )
    (net (code "61") (name "Net-(LD14-C)") (class "Default")
      (node (ref "LD14") (pin "1") (pinfunction "C_1") (pintype "passive"))
      (node (ref "R213") (pin "2") (pinfunction "2_2") (pintype "passive"))
    )
    (net (code "62") (name "Net-(LD15-C)") (class "Default")
      (node (ref "LD15") (pin "1") (pinfunction "C_1") (pintype "passive"))
      (node (ref "R212") (pin "2") (pinfunction "2_2") (pintype "passive"))
    )
    (net (code "63") (name "Net-(LD16-C)") (class "Default")
      (node (ref "LD16") (pin "1") (pinfunction "C_1") (pintype "passive"))
      (node (ref "R214") (pin "2") (pinfunction "2_2") (pintype "passive"))
    )
    (net (code "64") (name "P3V3") (class "Default")
      (node (ref "C454") (pin "2") (pinfunction "2_2") (pintype "passive"))
      (node (ref "IC36") (pin "36") (pinfunction "REG_IN_36") (pintype "power_in"))
      (node (ref "L11") (pin "2") (pinfunction "2_2") (pintype "passive"))
      (node (ref "L12") (pin "1") (pinfunction "1_1") (pintype "passive"))
      (node (ref "LD14") (pin "2") (pinfunction "A_2") (pintype "passive"))
      (node (ref "LD15") (pin "2") (pinfunction "A_2") (pintype "passive"))
      (node (ref "LD16") (pin "2") (pinfunction "A_2") (pintype "passive"))
      (node (ref "R211") (pin "2") (pinfunction "2_2") (pintype "passive"))
      (node (ref "R40") (pin "2") (pinfunction "2_2") (pintype "passive"))
    )
    (net (code "65") (name "unconnected-(IC36A-CLK125-Pad9)") (class "Default")
      (node (ref "IC36") (pin "9") (pinfunction "CLK125_9") (pintype "output"))
    )
    (net (code "66") (name "unconnected-(IC36A-HSDACN-Pad31)") (class "Default")
      (node (ref "IC36") (pin "31") (pinfunction "HSDACN_31") (pintype "output"))
    )
    (net (code "67") (name "unconnected-(IC36A-HSDACP-Pad32)") (class "Default")
      (node (ref "IC36") (pin "32") (pinfunction "HSDACP_32") (pintype "output"))
    )
    (net (code "68") (name "unconnected-(IC36A-TSTPT-Pad29)") (class "Default")
      (node (ref "IC36") (pin "29") (pinfunction "TSTPT_29") (pintype "output"))
    )
    (net (code "69") (name "unconnected-(J7-Pad14)") (class "Default")
      (node (ref "J7") (pin "14") (pinfunction "14_14") (pintype "bidirectional"))
    )
  )
)
